# LM76003.net
KiCad netlist of a schematic drawn in Altium Designer
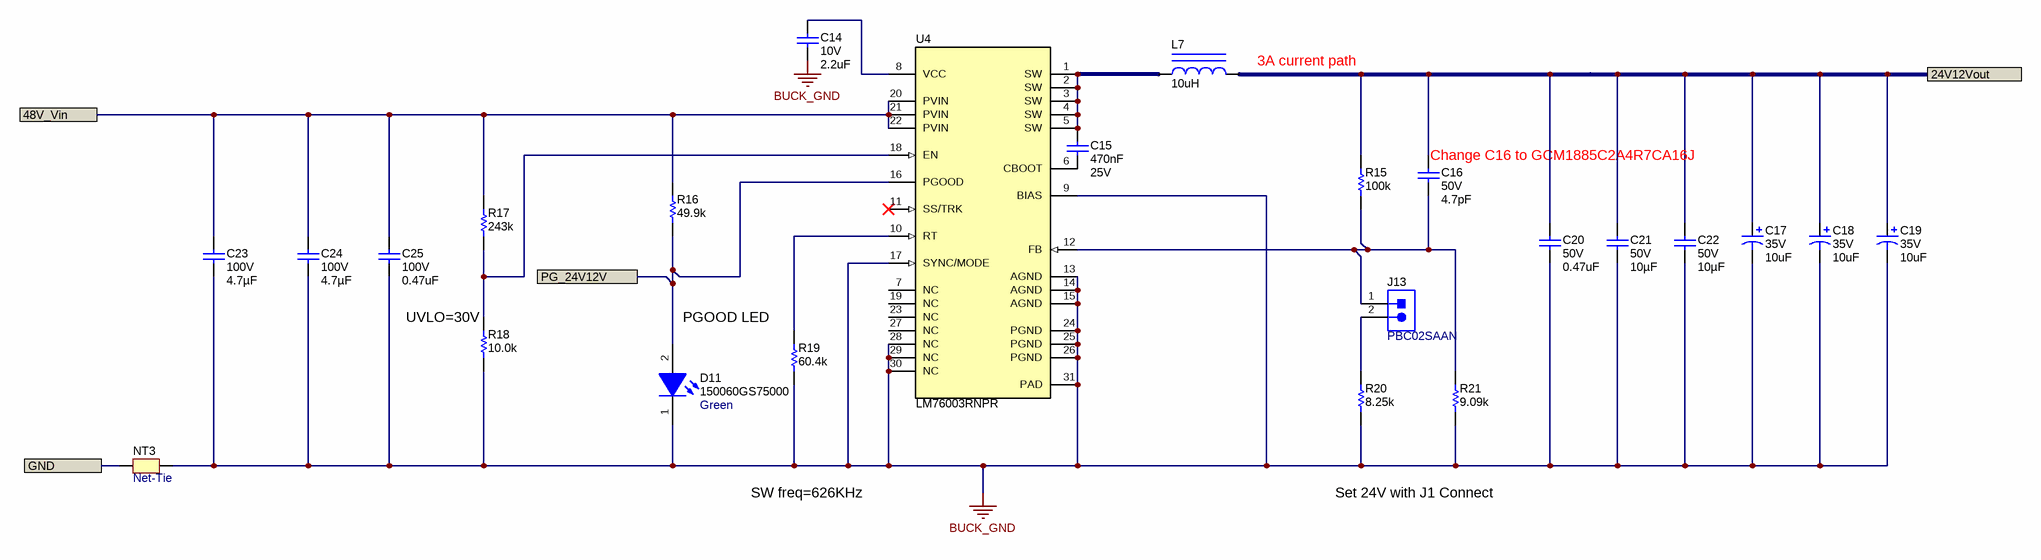
[diagram p0: LM76003.SchDoc]

(export (version "E")
  (design (tool "Eeschema 10.0.6"))
  (components
    (comp (ref "C14")
      (value "GRM188R71A225KE15D")
      (footprint "0603")
      (description "CAP, CERM, 2.2 uF, 10 V, +/- 10%, X7R, 0603")
      (fields
        (field (name "MANUFACTURER") "MuRata")
        (field (name "VDC_V") "10V")
        (field (name "VALUEDISPLAYED") "2.2uF")
        (field (name "PUBLISHER") "Texas Instruments")
      )
      (libsource (lib "Altium Vault - TI") (part "Capacitor"))
    )
    (comp (ref "C15")
      (value "GCM188R71E474KA64D")
      (footprint "0603")
      (description "CAP, CERM, 0.47 uF, 25 V, +/- 10%, X7R, AEC-Q200 Grade 1, 0603")
      (fields
        (field (name "MANUFACTURER") "MuRata")
        (field (name "CAP_F") "470nF")
        (field (name "VDC_V") "25V")
        (field (name "PUBLISHER") "Texas Instruments")
      )
      (libsource (lib "Altium Vault - TI") (part "Capacitor"))
    )
    (comp (ref "C16")
      (value "06035A4R7CAT2A")
      (footprint "0603")
      (description "CAP, CERM, 4.7 pF, 50 V, +/- 5%, C0G/NP0, 0603")
      (fields
        (field (name "MANUFACTURER") "AVX")
        (field (name "VDC_V") "50V")
        (field (name "VALUEDISPLAYED") "4.7pF")
        (field (name "PUBLISHER") "Texas Instruments")
      )
      (libsource (lib "Altium Vault - TI") (part "Capacitor"))
    )
    (comp (ref "C17")
      (value "593D106X9035D2TE3")
      (footprint "7343-31")
      (description "CAP, TA, 10 uF, 35 V, +/- 10%, 0.3 ohm, SMD")
      (fields
        (field (name "MANUFACTURER") "Vishay-Sprague")
        (field (name "VDC_V") "35V")
        (field (name "VALUEDISPLAYED") "10uF")
        (field (name "PUBLISHER") "Texas Instruments")
      )
      (libsource (lib "Altium Vault - TI") (part "Cap_Polarized"))
    )
    (comp (ref "C18")
      (value "593D106X9035D2TE3")
      (footprint "7343-31")
      (description "CAP, TA, 10 uF, 35 V, +/- 10%, 0.3 ohm, SMD")
      (fields
        (field (name "MANUFACTURER") "Vishay-Sprague")
        (field (name "VDC_V") "35V")
        (field (name "VALUEDISPLAYED") "10uF")
        (field (name "PUBLISHER") "Texas Instruments")
      )
      (libsource (lib "Altium Vault - TI") (part "Cap_Polarized"))
    )
    (comp (ref "C19")
      (value "593D106X9035D2TE3")
      (footprint "7343-31")
      (description "CAP, TA, 10 uF, 35 V, +/- 10%, 0.3 ohm, SMD")
      (fields
        (field (name "MANUFACTURER") "Vishay-Sprague")
        (field (name "VDC_V") "35V")
        (field (name "VALUEDISPLAYED") "10uF")
        (field (name "PUBLISHER") "Texas Instruments")
      )
      (libsource (lib "Altium Vault - TI") (part "Cap_Polarized"))
    )
    (comp (ref "C20")
      (value "GRM21BR71H474KA88L")
      (footprint "0805_HV")
      (description "CAP, CERM, 0.47 uF, 50 V, +/- 10%, X7R, 0805")
      (fields
        (field (name "MANUFACTURER") "MuRata")
        (field (name "VDC_V") "50V")
        (field (name "VALUEDISPLAYED") "0.47uF")
        (field (name "PUBLISHER") "Texas Instruments")
      )
      (libsource (lib "Altium Vault - TI") (part "Capacitor"))
    )
    (comp (ref "C21")
      (value "GRJ32ER71H106KE11L")
      (footprint "1210_280")
      (description "CAP, CERM, 10 µF, 50 V,+/- 10%, X7R, 1210")
      (fields
        (field (name "MANUFACTURER") "MuRata")
        (field (name "VDC_V") "50V")
        (field (name "VALUEDISPLAYED") "10µF")
      )
      (libsource (lib "Altium Vault - TI") (part "Capacitor"))
    )
    (comp (ref "C22")
      (value "GRJ32ER71H106KE11L")
      (footprint "1210_280")
      (description "CAP, CERM, 10 µF, 50 V,+/- 10%, X7R, 1210")
      (fields
        (field (name "MANUFACTURER") "MuRata")
        (field (name "VDC_V") "50V")
        (field (name "VALUEDISPLAYED") "10µF")
      )
      (libsource (lib "Altium Vault - TI") (part "Capacitor"))
    )
    (comp (ref "C23")
      (value "GCM32DC72A475KE02L")
      (footprint "1210_220")
      (description "CAP, CERM, 4.7 µF, 100 V,+/- 10%, X7S, AEC-Q200 Grade 1, 1210")
      (fields
        (field (name "MANUFACTURER") "MuRata")
        (field (name "VDC_V") "100V")
        (field (name "VALUEDISPLAYED") "4.7µF")
      )
      (libsource (lib "Altium Vault - TI") (part "Capacitor"))
    )
    (comp (ref "C24")
      (value "GCM32DC72A475KE02L")
      (footprint "1210_220")
      (description "CAP, CERM, 4.7 µF, 100 V,+/- 10%, X7S, AEC-Q200 Grade 1, 1210")
      (fields
        (field (name "MANUFACTURER") "MuRata")
        (field (name "VDC_V") "100V")
        (field (name "VALUEDISPLAYED") "4.7µF")
      )
      (libsource (lib "Altium Vault - TI") (part "Capacitor"))
    )
    (comp (ref "C25")
      (value "GRM21BR72A474KA73L")
      (footprint "0805_HV")
      (description "CAP, CERM, 0.47 uF, 100 V, +/- 10%, X7R, 0805")
      (fields
        (field (name "MANUFACTURER") "MuRata")
        (field (name "VDC_V") "100V")
        (field (name "VALUEDISPLAYED") "0.47uF")
        (field (name "PUBLISHER") "Texas Instruments")
      )
      (libsource (lib "Altium Vault - TI") (part "Capacitor"))
    )
    (comp (ref "D11")
      (value "150060GS75000")
      (footprint "WL-SMCW_GREEN")
      (description "LED, Green, SMD")
      (fields (field (name "ALTIUM_VALUE") "Green") (field (name "MANUFACTURER") "Wurth Elektronik"))
      (libsource (lib "Altium Vault - TI") (part "LED_A2_K1"))
    )
    (comp (ref "J13")
      (value "PBC02SAAN")
      (footprint "Sullins_PBC02SAAN")
      (description "Header, 100mil, 2x1, Gold, TH")
      (fields
        (field (name "MANUFACTURER") "Sullins Connector Solutions")
        (field (name "PUBLISHER") "Texas Instruments")
      )
      (libsource (lib "Altium Vault - TI") (part "Header_2x1"))
    )
    (comp (ref "L7")
      (value "74437346100")
      (footprint "WE-LHMI_7030")
      (description "Inductor, Shielded Drum Core, Powdered Iron, 10 uH, 3 A, 0.075 ohm, SMD")
      (fields
        (field (name "MANUFACTURER") "Wurth Elektronik")
        (field (name "VALUEDISPLAYED") "10uH")
        (field (name "PUBLISHER") "Texas Instruments")
      )
      (libsource (lib "Altium Vault - TI") (part "Inductor_Iron"))
    )
    (comp (ref "NT3")
      (value "Net-Tie")
      (footprint "Net-Tie_50milWide_30milLong")
      (description "Single point connection between nets.")
      (libsource (lib "Altium Vault - TI") (part "Net-Tie"))
    )
    (comp (ref "R15")
      (value "CRCW0402100KFKED")
      (footprint "0402")
      (description "RES, 100 k, 1%, 0.063 W, AEC-Q200 Grade 0, 0402")
      (fields (field (name "MANUFACTURER") "Vishay-Dale") (field (name "VALUEDISPLAYED") "100k"))
      (libsource (lib "Altium Vault - TI") (part "Resistor"))
    )
    (comp (ref "R16")
      (value "CRCW060349K9FKEA")
      (footprint "0603")
      (description "RES, 49.9 k, 1%, 0.1 W, 0603")
      (fields
        (field (name "MANUFACTURER") "Vishay-Dale")
        (field (name "VALUEDISPLAYED") "49.9k")
        (field (name "PUBLISHER") "Texas Instruments")
      )
      (libsource (lib "Altium Vault - TI") (part "Resistor"))
    )
    (comp (ref "R17")
      (value "CRCW0402243KFKED")
      (footprint "0402")
      (description "RES, 243 k, 1%, 0.063 W, AEC-Q200 Grade 0, 0402")
      (fields (field (name "MANUFACTURER") "Vishay-Dale") (field (name "VALUEDISPLAYED") "243k"))
      (libsource (lib "Altium Vault - TI") (part "Resistor"))
    )
    (comp (ref "R18")
      (value "CRCW040210K0FKED")
      (footprint "0402")
      (description "RES, 10.0 k, 1%, 0.063 W, AEC-Q200 Grade 0, 0402")
      (fields (field (name "MANUFACTURER") "Vishay-Dale") (field (name "VALUEDISPLAYED") "10.0k"))
      (libsource (lib "Altium Vault - TI") (part "Resistor"))
    )
    (comp (ref "R19")
      (value "CRCW040260K4FKED")
      (footprint "0402")
      (description "RES, 60.4 k, 1%, 0.063 W, AEC-Q200 Grade 0, 0402")
      (fields (field (name "MANUFACTURER") "Vishay-Dale") (field (name "VALUEDISPLAYED") "60.4k"))
      (libsource (lib "Altium Vault - TI") (part "Resistor"))
    )
    (comp (ref "R20")
      (value "CRCW04028K25FKED")
      (footprint "0402")
      (description "RES, 8.25 k, 1%, 0.063 W, AEC-Q200 Grade 0, 0402")
      (fields (field (name "MANUFACTURER") "Vishay-Dale") (field (name "VALUEDISPLAYED") "8.25k"))
      (libsource (lib "Altium Vault - TI") (part "Resistor"))
    )
    (comp (ref "R21")
      (value "CRCW04029K09FKED")
      (footprint "0402")
      (description "RES, 9.09 k, 1%, 0.063 W, AEC-Q200 Grade 0, 0402")
      (fields (field (name "VALUEDISPLAYED") "9.09k") (field (name "MANUFACTURER") "Vishay-Dale"))
      (libsource (lib "Altium Vault - TI") (part "Resistor"))
    )
    (comp (ref "U4")
      (value "LM76003RNPR")
      (footprint "RNP0030B")
      (description "SIMPLE SWITCHER 3.5V to 60V 3.5A Synchronous Step-Down Voltage Regulator, RNP0030B (WQFN-30)")
      (fields
        (field (name "PARTNUMBER") "LM76003RNPR")
        (field (name "MANUFACTURER") "Texas Instruments")
        (field (name "ALTERNATE PARTNUMBER") "LM76003RNPT")
        (field (name "PUBLISHER") "Texas Instruments")
      )
      (libsource (lib "Altium Vault - TI") (part "LM76003"))
    )
  )
  (nets
    (net (code "1") (name "/24V12Vout") (class "Default")
      (node (ref "C16") (pin "1") (pinfunction "1_1") (pintype "passive"))
      (node (ref "C17") (pin "1") (pinfunction "+_1") (pintype "passive"))
      (node (ref "C18") (pin "1") (pinfunction "+_1") (pintype "passive"))
      (node (ref "C19") (pin "1") (pinfunction "+_1") (pintype "passive"))
      (node (ref "C20") (pin "1") (pinfunction "1_1") (pintype "passive"))
      (node (ref "C21") (pin "1") (pinfunction "1_1") (pintype "passive"))
      (node (ref "C22") (pin "1") (pinfunction "1_1") (pintype "passive"))
      (node (ref "L7") (pin "2") (pinfunction "2_2") (pintype "passive"))
      (node (ref "R15") (pin "2") (pinfunction "2_2") (pintype "passive"))
    )
    (net (code "2") (name "/48V_Vin") (class "Default")
      (node (ref "C23") (pin "1") (pinfunction "1_1") (pintype "passive"))
      (node (ref "C24") (pin "1") (pinfunction "1_1") (pintype "passive"))
      (node (ref "C25") (pin "1") (pinfunction "1_1") (pintype "passive"))
      (node (ref "R16") (pin "2") (pinfunction "2_2") (pintype "passive"))
      (node (ref "R17") (pin "2") (pinfunction "2_2") (pintype "passive"))
      (node (ref "U4") (pin "20") (pinfunction "PVIN_20") (pintype "power_in"))
      (node (ref "U4") (pin "21") (pinfunction "PVIN_21") (pintype "power_in"))
      (node (ref "U4") (pin "22") (pinfunction "PVIN_22") (pintype "power_in"))
    )
    (net (code "3") (name "/GND") (class "Default")
      (node (ref "NT3") (pin "1") (pinfunction "1_1") (pintype "passive"))
    )
    (net (code "4") (name "/PG_24V12V") (class "Default")
      (node (ref "D11") (pin "2") (pinfunction "A_2") (pintype "passive"))
      (node (ref "R16") (pin "1") (pinfunction "1_1") (pintype "passive"))
      (node (ref "U4") (pin "16") (pinfunction "PGOOD_16") (pintype "open_collector"))
    )
    (net (code "5") (name "BUCK_GND") (class "Default")
      (node (ref "C14") (pin "2") (pinfunction "2_2") (pintype "passive"))
      (node (ref "C17") (pin "2") (pinfunction "-_2") (pintype "passive"))
      (node (ref "C18") (pin "2") (pinfunction "-_2") (pintype "passive"))
      (node (ref "C19") (pin "2") (pinfunction "-_2") (pintype "passive"))
      (node (ref "C20") (pin "2") (pinfunction "2_2") (pintype "passive"))
      (node (ref "C21") (pin "2") (pinfunction "2_2") (pintype "passive"))
      (node (ref "C22") (pin "2") (pinfunction "2_2") (pintype "passive"))
      (node (ref "C23") (pin "2") (pinfunction "2_2") (pintype "passive"))
      (node (ref "C24") (pin "2") (pinfunction "2_2") (pintype "passive"))
      (node (ref "C25") (pin "2") (pinfunction "2_2") (pintype "passive"))
      (node (ref "D11") (pin "1") (pinfunction "K_1") (pintype "passive"))
      (node (ref "NT3") (pin "2") (pinfunction "2_2") (pintype "passive"))
      (node (ref "R18") (pin "1") (pinfunction "1_1") (pintype "passive"))
      (node (ref "R19") (pin "1") (pinfunction "1_1") (pintype "passive"))
      (node (ref "R20") (pin "1") (pinfunction "1_1") (pintype "passive"))
      (node (ref "R21") (pin "1") (pinfunction "1_1") (pintype "passive"))
      (node (ref "U4") (pin "13") (pinfunction "AGND_13") (pintype "power_in"))
      (node (ref "U4") (pin "14") (pinfunction "AGND_14") (pintype "power_in"))
      (node (ref "U4") (pin "15") (pinfunction "AGND_15") (pintype "power_in"))
      (node (ref "U4") (pin "17") (pinfunction "SYNC/MODE_17") (pintype "input"))
      (node (ref "U4") (pin "24") (pinfunction "PGND_24") (pintype "power_in"))
      (node (ref "U4") (pin "25") (pinfunction "PGND_25") (pintype "power_in"))
      (node (ref "U4") (pin "26") (pinfunction "PGND_26") (pintype "power_in"))
      (node (ref "U4") (pin "28") (pinfunction "NC_28") (pintype "passive"))
      (node (ref "U4") (pin "29") (pinfunction "NC_29") (pintype "passive"))
      (node (ref "U4") (pin "30") (pinfunction "NC_30") (pintype "passive"))
      (node (ref "U4") (pin "31") (pinfunction "PAD_31") (pintype "power_in"))
      (node (ref "U4") (pin "9") (pinfunction "BIAS_9") (pintype "passive"))
    )
    (net (code "6") (name "Net-(C15-Pad1)") (class "Default")
      (node (ref "C15") (pin "1") (pinfunction "1_1") (pintype "passive"))
      (node (ref "L7") (pin "1") (pinfunction "1_1") (pintype "passive"))
      (node (ref "U4") (pin "1") (pinfunction "SW_1") (pintype "power_in"))
      (node (ref "U4") (pin "2") (pinfunction "SW_2") (pintype "power_in"))
      (node (ref "U4") (pin "3") (pinfunction "SW_3") (pintype "power_in"))
      (node (ref "U4") (pin "4") (pinfunction "SW_4") (pintype "power_in"))
      (node (ref "U4") (pin "5") (pinfunction "SW_5") (pintype "power_in"))
    )
    (net (code "7") (name "Net-(J13-Pad2)") (class "Default")
      (node (ref "J13") (pin "2") (pinfunction "2_2") (pintype "passive"))
      (node (ref "R20") (pin "2") (pinfunction "2_2") (pintype "passive"))
    )
    (net (code "8") (name "Net-(U4-CBOOT)") (class "Default")
      (node (ref "C15") (pin "2") (pinfunction "2_2") (pintype "passive"))
      (node (ref "U4") (pin "6") (pinfunction "CBOOT_6") (pintype "power_in"))
    )
    (net (code "9") (name "Net-(U4-EN)") (class "Default")
      (node (ref "R17") (pin "1") (pinfunction "1_1") (pintype "passive"))
      (node (ref "R18") (pin "2") (pinfunction "2_2") (pintype "passive"))
      (node (ref "U4") (pin "18") (pinfunction "EN_18") (pintype "input"))
    )
    (net (code "10") (name "Net-(U4-FB)") (class "Default")
      (node (ref "C16") (pin "2") (pinfunction "2_2") (pintype "passive"))
      (node (ref "J13") (pin "1") (pinfunction "1_1") (pintype "passive"))
      (node (ref "R15") (pin "1") (pinfunction "1_1") (pintype "passive"))
      (node (ref "R21") (pin "2") (pinfunction "2_2") (pintype "passive"))
      (node (ref "U4") (pin "12") (pinfunction "FB_12") (pintype "input"))
    )
    (net (code "11") (name "Net-(U4-RT)") (class "Default")
      (node (ref "R19") (pin "2") (pinfunction "2_2") (pintype "passive"))
      (node (ref "U4") (pin "10") (pinfunction "RT_10") (pintype "input"))
    )
    (net (code "12") (name "Net-(U4-VCC)") (class "Default")
      (node (ref "C14") (pin "1") (pinfunction "1_1") (pintype "passive"))
      (node (ref "U4") (pin "8") (pinfunction "VCC_8") (pintype "power_in"))
    )
    (net (code "13") (name "unconnected-(U4-NC-Pad7)") (class "Default")
      (node (ref "U4") (pin "7") (pinfunction "NC_7") (pintype "passive"))
    )
    (net (code "14") (name "unconnected-(U4-NC-Pad19)") (class "Default")
      (node (ref "U4") (pin "19") (pinfunction "NC_19") (pintype "passive"))
    )
    (net (code "15") (name "unconnected-(U4-NC-Pad23)") (class "Default")
      (node (ref "U4") (pin "23") (pinfunction "NC_23") (pintype "passive"))
    )
    (net (code "16") (name "unconnected-(U4-NC-Pad27)") (class "Default")
      (node (ref "U4") (pin "27") (pinfunction "NC_27") (pintype "passive"))
    )
    (net (code "17") (name "unconnected-(U4-SS{slash}TRK-Pad11)") (class "Default")
      (node (ref "U4") (pin "11") (pinfunction "SS/TRK_11") (pintype "input+no_connect"))
    )
  )
)
